# USB.net
KiCad netlist of a schematic drawn in Altium Designer
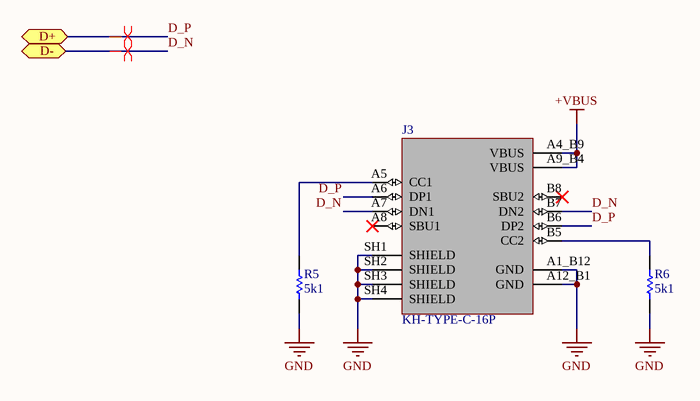
[diagram p0: USB.SchDoc]

(export (version "E")
  (design (tool "Eeschema 10.0.6"))
  (components
    (comp (ref "J3")
      (value "KH-TYPE-C-16P")
      (footprint "KINGHELM_KH-TYPE-C-16P")
      (fields (field (name "MF") "kinghelm"))
      (libsource (lib "Connectors") (part "KH-TYPE-C-16P"))
    )
    (comp (ref "R5")
      (value "5k1")
      (footprint "0805 Resistor")
      (fields (field (name "Comment") "Generic Resistor 5k1 0805"))
      (libsource (lib "Passives") (part "Generic Resistor 5k1 0805"))
    )
    (comp (ref "R6")
      (value "5k1")
      (footprint "0805 Resistor")
      (fields (field (name "Comment") "Generic Resistor 5k1 0805"))
      (libsource (lib "Passives") (part "Generic Resistor 5k1 0805"))
    )
  )
  (nets
    (net (code "1") (name "+VBUS") (class "Default")
      (node (ref "J3") (pin "A4_B9") (pinfunction "VBUS_A4_B9") (pintype "power_in"))
      (node (ref "J3") (pin "A9_B4") (pinfunction "VBUS_A9_B4") (pintype "power_in"))
    )
    (net (code "2") (name "/D_N") (class "Default")
      (node (ref "J3") (pin "A7") (pinfunction "DN1_A7") (pintype "bidirectional"))
      (node (ref "J3") (pin "B7") (pinfunction "DN2_B7") (pintype "bidirectional"))
    )
    (net (code "3") (name "/D_P") (class "Default")
      (node (ref "J3") (pin "A6") (pinfunction "DP1_A6") (pintype "bidirectional"))
      (node (ref "J3") (pin "B6") (pinfunction "DP2_B6") (pintype "bidirectional"))
    )
    (net (code "4") (name "GND") (class "Default")
      (node (ref "J3") (pin "A12_B1") (pinfunction "GND_A12_B1") (pintype "power_in"))
      (node (ref "J3") (pin "A1_B12") (pinfunction "GND_A1_B12") (pintype "power_in"))
      (node (ref "J3") (pin "SH1") (pinfunction "SHIELD_SH1") (pintype "passive"))
      (node (ref "J3") (pin "SH2") (pinfunction "SHIELD_SH2") (pintype "passive"))
      (node (ref "J3") (pin "SH3") (pinfunction "SHIELD_SH3") (pintype "passive"))
      (node (ref "J3") (pin "SH4") (pinfunction "SHIELD_SH4") (pintype "passive"))
      (node (ref "R5") (pin "1") (pinfunction "1_1") (pintype "passive"))
      (node (ref "R6") (pin "1") (pinfunction "1_1") (pintype "passive"))
    )
    (net (code "5") (name "Net-(J3-CC1)") (class "Default")
      (node (ref "J3") (pin "A5") (pinfunction "CC1_A5") (pintype "bidirectional"))
      (node (ref "R5") (pin "2") (pinfunction "2_2") (pintype "passive"))
    )
    (net (code "6") (name "Net-(J3-CC2)") (class "Default")
      (node (ref "J3") (pin "B5") (pinfunction "CC2_B5") (pintype "bidirectional"))
      (node (ref "R6") (pin "2") (pinfunction "2_2") (pintype "passive"))
    )
    (net (code "7") (name "unconnected-(J3-SBU1-PadA8)") (class "Default")
      (node (ref "J3") (pin "A8") (pinfunction "SBU1_A8") (pintype "bidirectional+no_connect"))
    )
    (net (code "8") (name "unconnected-(J3-SBU2-PadB8)") (class "Default")
      (node (ref "J3") (pin "B8") (pinfunction "SBU2_B8") (pintype "bidirectional+no_connect"))
    )
  )
)
